# sensor.net
KiCad netlist of a schematic drawn in Altium Designer
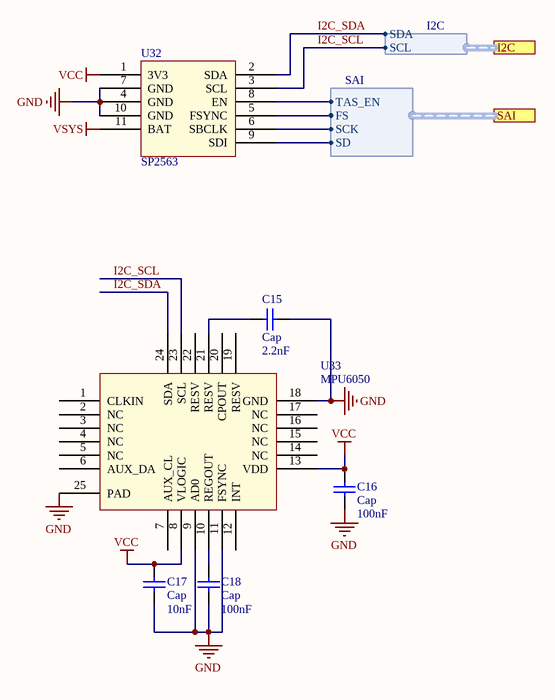
[diagram p0: sensor.SchDoc]

(export (version "E")
  (design (tool "Eeschema 10.0.6"))
  (components
    (comp (ref "C15")
      (value "Cap")
      (footprint "0402")
      (description "Capacitor")
      (fields (field (name "ALTIUM_VALUE") "2.2nF") (field (name "PUBLISHER") "Altium Limited"))
      (libsource (lib "Miscellaneous Devices") (part "Cap"))
    )
    (comp (ref "C16")
      (value "Cap")
      (footprint "0402")
      (description "Capacitor")
      (fields (field (name "ALTIUM_VALUE") "100nF") (field (name "PUBLISHER") "Altium Limited"))
      (libsource (lib "Miscellaneous Devices") (part "Cap"))
    )
    (comp (ref "C17")
      (value "Cap")
      (footprint "0402")
      (description "Capacitor")
      (fields (field (name "ALTIUM_VALUE") "10nF") (field (name "PUBLISHER") "Altium Limited"))
      (libsource (lib "Miscellaneous Devices") (part "Cap"))
    )
    (comp (ref "C18")
      (value "Cap")
      (footprint "0402")
      (description "Capacitor")
      (fields (field (name "ALTIUM_VALUE") "100nF") (field (name "PUBLISHER") "Altium Limited"))
      (libsource (lib "Miscellaneous Devices") (part "Cap"))
    )
    (comp (ref "U32") (value "SP2563") (footprint "SP2563") (libsource (lib "cl_sch") (part "SP2563")))
    (comp (ref "U33")
      (value "MPU6050")
      (footprint "QFN24_AW9523B")
      (libsource (lib "cl_sch") (part "MPU6050"))
    )
  )
  (nets
    (net (code "3") (name "/FS") (class "Default")
      (node (ref "U32") (pin "5") (pinfunction "FSYNC_5") (pintype "passive"))
    )
    (net (code "4") (name "/I2C_SCL") (class "Default")
      (node (ref "U32") (pin "3") (pinfunction "SCL_3") (pintype "passive"))
      (node (ref "U33") (pin "23") (pinfunction "SCL_23") (pintype "passive"))
    )
    (net (code "5") (name "/I2C_SDA") (class "Default")
      (node (ref "U32") (pin "2") (pinfunction "SDA_2") (pintype "passive"))
      (node (ref "U33") (pin "24") (pinfunction "SDA_24") (pintype "passive"))
    )
    (net (code "6") (name "/SCK") (class "Default")
      (node (ref "U32") (pin "6") (pinfunction "SBCLK_6") (pintype "passive"))
    )
    (net (code "7") (name "/SD") (class "Default")
      (node (ref "U32") (pin "9") (pinfunction "SDI_9") (pintype "passive"))
    )
    (net (code "8") (name "/TAS_EN") (class "Default")
      (node (ref "U32") (pin "8") (pinfunction "EN_8") (pintype "passive"))
    )
    (net (code "11") (name "GND") (class "Default")
      (node (ref "C15") (pin "1") (pinfunction "1_1") (pintype "passive"))
      (node (ref "C16") (pin "2") (pinfunction "2_2") (pintype "passive"))
      (node (ref "C17") (pin "2") (pinfunction "2_2") (pintype "passive"))
      (node (ref "C18") (pin "2") (pinfunction "2_2") (pintype "passive"))
      (node (ref "U32") (pin "10") (pinfunction "GND_10") (pintype "passive"))
      (node (ref "U32") (pin "4") (pinfunction "GND_4") (pintype "passive"))
      (node (ref "U32") (pin "7") (pinfunction "GND_7") (pintype "passive"))
      (node (ref "U33") (pin "11") (pinfunction "FSYNC_11") (pintype "passive"))
      (node (ref "U33") (pin "18") (pinfunction "GND_18") (pintype "passive"))
      (node (ref "U33") (pin "25") (pinfunction "PAD_25") (pintype "passive"))
      (node (ref "U33") (pin "9") (pinfunction "AD0_9") (pintype "passive"))
    )
    (net (code "12") (name "Net-(C15-Pad2)") (class "Default")
      (node (ref "C15") (pin "2") (pinfunction "2_2") (pintype "passive"))
      (node (ref "U33") (pin "21") (pinfunction "RESV_21") (pintype "passive"))
    )
    (net (code "13") (name "Net-(U33-REGOUT)") (class "Default")
      (node (ref "C18") (pin "1") (pinfunction "1_1") (pintype "passive"))
      (node (ref "U33") (pin "10") (pinfunction "REGOUT_10") (pintype "passive"))
    )
    (net (code "14") (name "VCC") (class "Default")
      (node (ref "C16") (pin "1") (pinfunction "1_1") (pintype "passive"))
      (node (ref "C17") (pin "1") (pinfunction "1_1") (pintype "passive"))
      (node (ref "U32") (pin "1") (pinfunction "3V3_1") (pintype "passive"))
      (node (ref "U33") (pin "13") (pinfunction "VDD_13") (pintype "passive"))
      (node (ref "U33") (pin "8") (pinfunction "VLOGIC_8") (pintype "passive"))
    )
    (net (code "15") (name "VSYS") (class "Default")
      (node (ref "U32") (pin "11") (pinfunction "BAT_11") (pintype "passive"))
    )
    (net (code "16") (name "unconnected-(U33-AUX_CL-Pad7)") (class "Default")
      (node (ref "U33") (pin "7") (pinfunction "AUX_CL_7") (pintype "passive"))
    )
    (net (code "17") (name "unconnected-(U33-AUX_DA-Pad6)") (class "Default")
      (node (ref "U33") (pin "6") (pinfunction "AUX_DA_6") (pintype "passive"))
    )
    (net (code "18") (name "unconnected-(U33-CLKIN-Pad1)") (class "Default")
      (node (ref "U33") (pin "1") (pinfunction "CLKIN_1") (pintype "passive"))
    )
    (net (code "19") (name "unconnected-(U33-CPOUT-Pad20)") (class "Default")
      (node (ref "U33") (pin "20") (pinfunction "CPOUT_20") (pintype "passive"))
    )
    (net (code "20") (name "unconnected-(U33-INT-Pad12)") (class "Default")
      (node (ref "U33") (pin "12") (pinfunction "INT_12") (pintype "passive"))
    )
    (net (code "21") (name "unconnected-(U33-NC-Pad2)") (class "Default")
      (node (ref "U33") (pin "2") (pinfunction "NC_2") (pintype "passive"))
    )
    (net (code "22") (name "unconnected-(U33-NC-Pad3)") (class "Default")
      (node (ref "U33") (pin "3") (pinfunction "NC_3") (pintype "passive"))
    )
    (net (code "23") (name "unconnected-(U33-NC-Pad4)") (class "Default")
      (node (ref "U33") (pin "4") (pinfunction "NC_4") (pintype "passive"))
    )
    (net (code "24") (name "unconnected-(U33-NC-Pad5)") (class "Default")
      (node (ref "U33") (pin "5") (pinfunction "NC_5") (pintype "passive"))
    )
    (net (code "25") (name "unconnected-(U33-NC-Pad14)") (class "Default")
      (node (ref "U33") (pin "14") (pinfunction "NC_14") (pintype "passive"))
    )
    (net (code "26") (name "unconnected-(U33-NC-Pad15)") (class "Default")
      (node (ref "U33") (pin "15") (pinfunction "NC_15") (pintype "passive"))
    )
    (net (code "27") (name "unconnected-(U33-NC-Pad16)") (class "Default")
      (node (ref "U33") (pin "16") (pinfunction "NC_16") (pintype "passive"))
    )
    (net (code "28") (name "unconnected-(U33-NC-Pad17)") (class "Default")
      (node (ref "U33") (pin "17") (pinfunction "NC_17") (pintype "passive"))
    )
    (net (code "29") (name "unconnected-(U33-RESV-Pad19)") (class "Default")
      (node (ref "U33") (pin "19") (pinfunction "RESV_19") (pintype "passive"))
    )
    (net (code "30") (name "unconnected-(U33-RESV-Pad22)") (class "Default")
      (node (ref "U33") (pin "22") (pinfunction "RESV_22") (pintype "passive"))
    )
  )
)
